# CutMonitor_Opto.net
KiCad netlist of a schematic drawn in Altium Designer
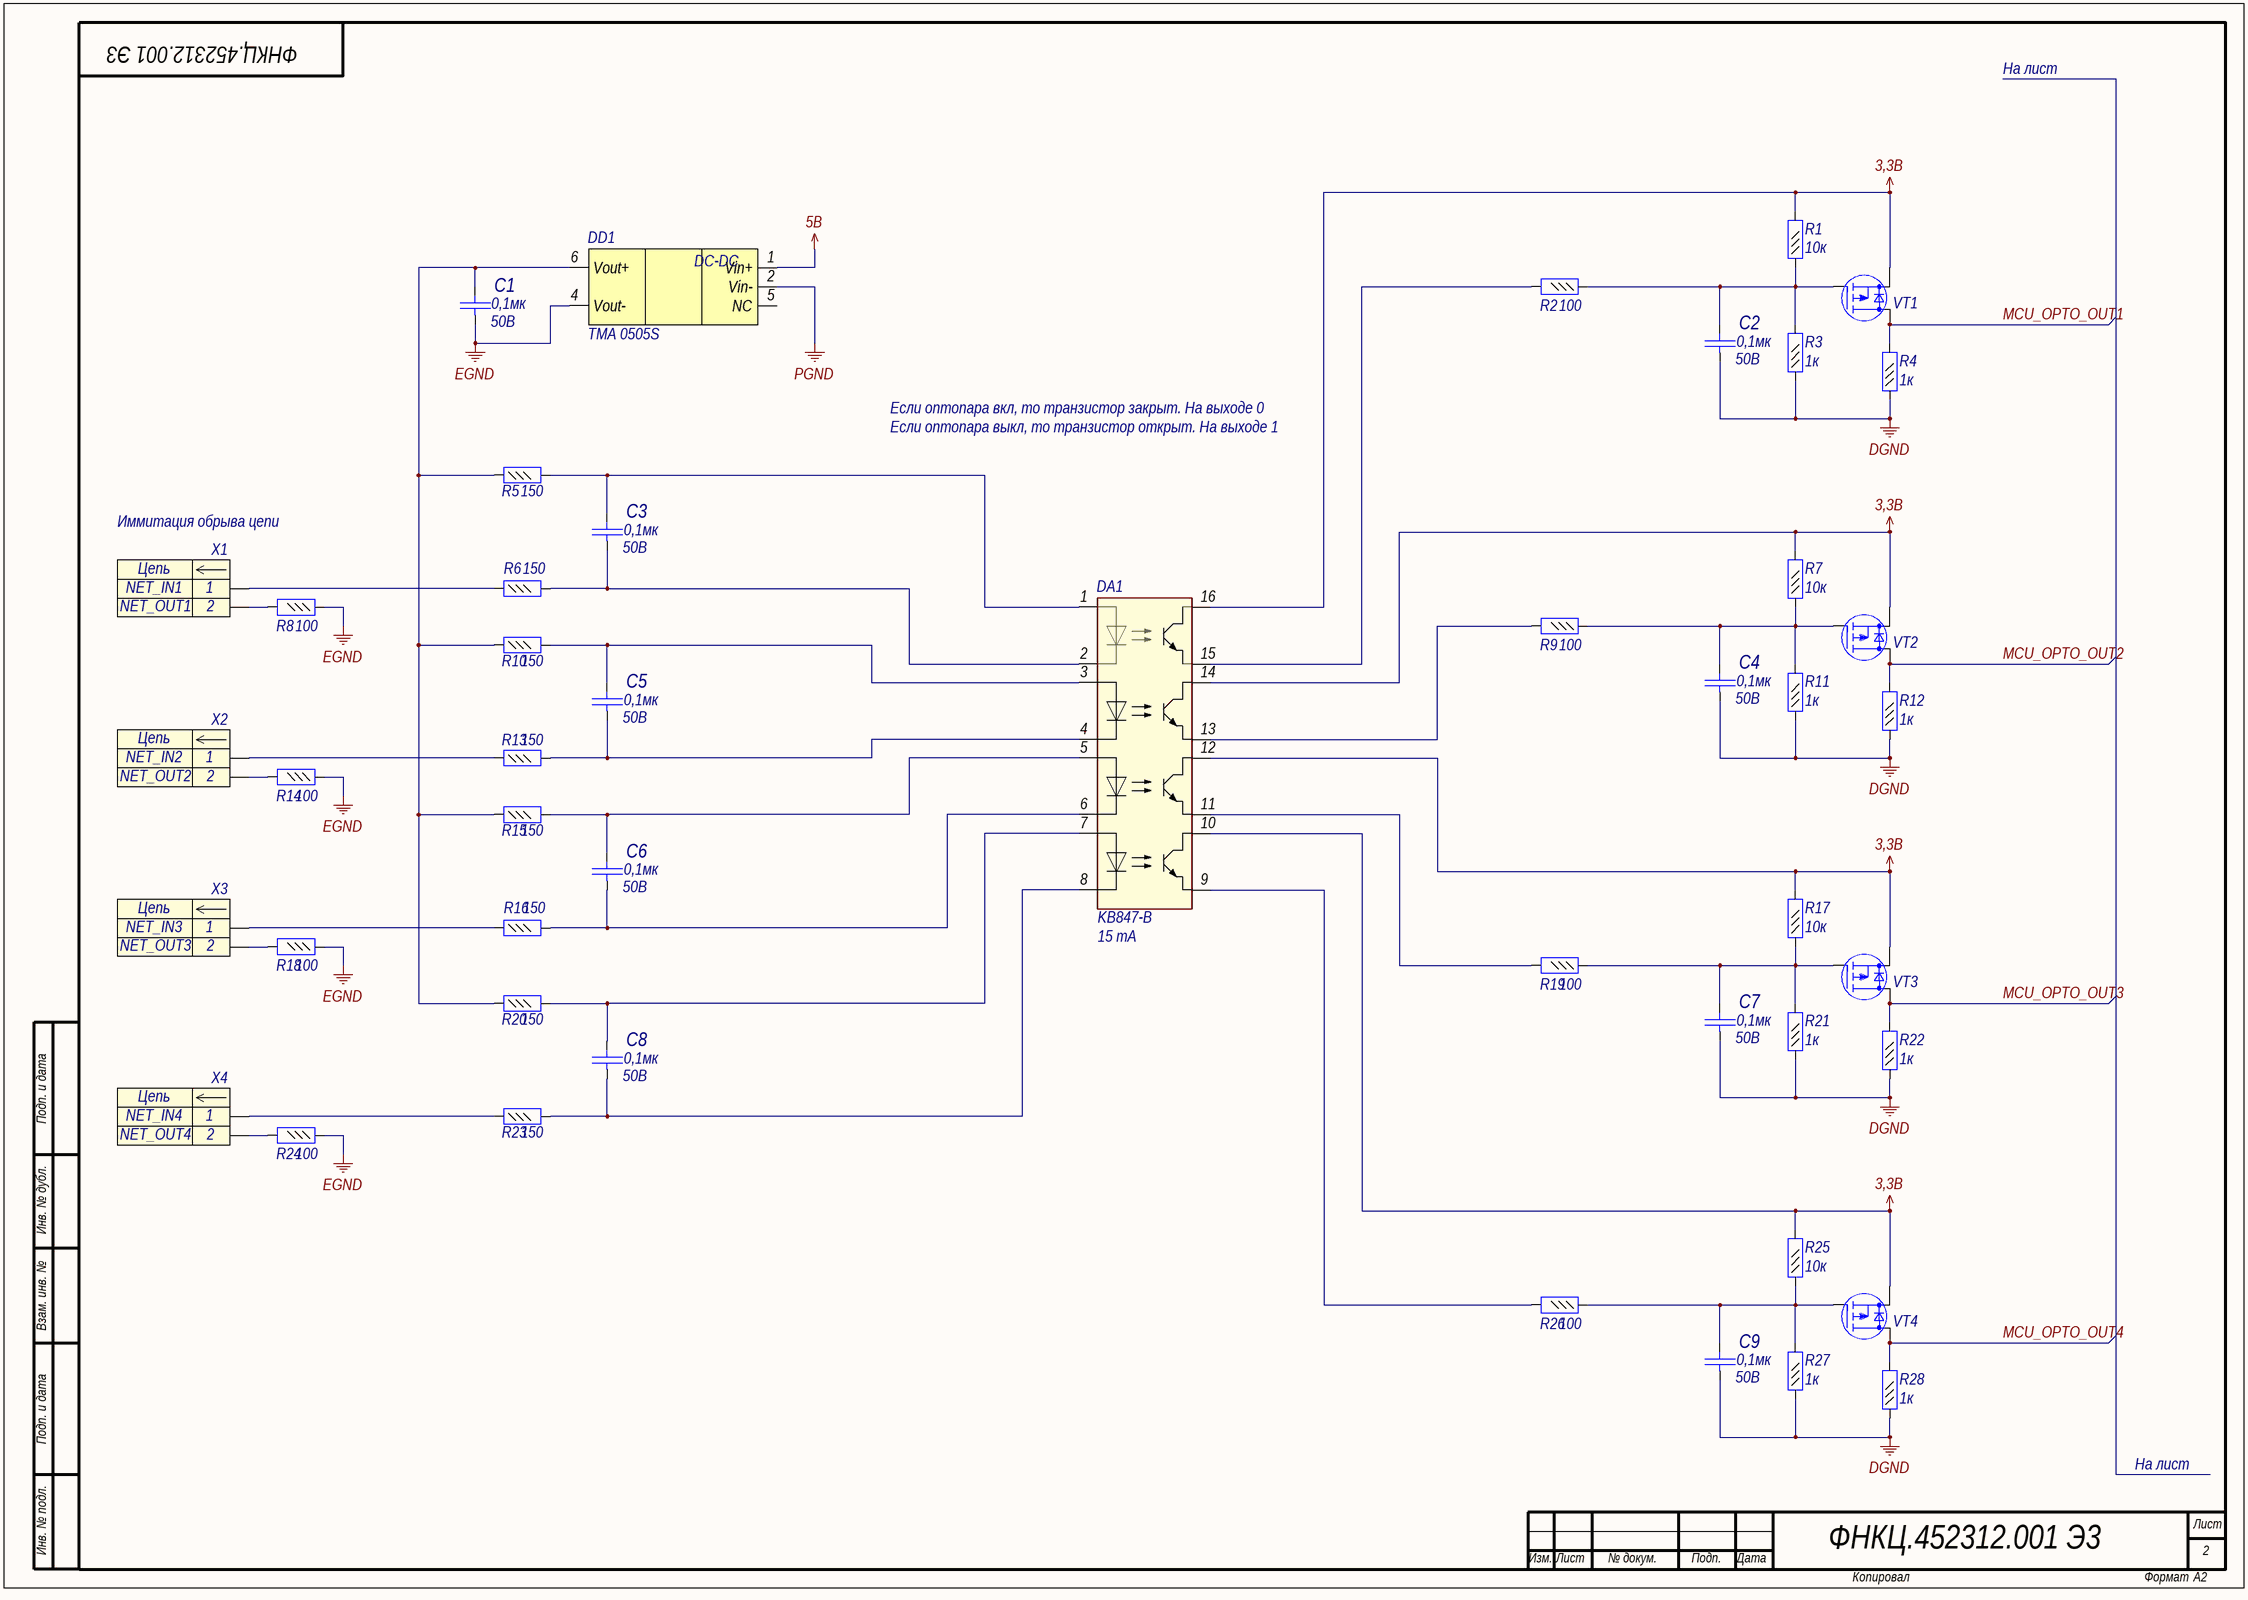
[diagram p0: CutMonitor_Opto.SchDoc]

(export (version "E")
  (design (tool "Eeschema 10.0.6"))
  (components
    (comp (ref "C1")
      (value "0,1мк")
      (footprint "C0603")
      (description "Конденсатор")
      (fields
        (field (name "VOLTAGE") "50B")
        (field (name "PART NUMBER") "GRM188R71H104KA93D")
        (field (name "Comment") "Capacitor")
      )
      (libsource (lib "MOP44") (part "Capacitor"))
    )
    (comp (ref "C2")
      (value "0,1мк")
      (footprint "C0603")
      (description "Конденсатор")
      (fields
        (field (name "VOLTAGE") "50B")
        (field (name "PART NUMBER") "GRM188R71H104KA93D")
        (field (name "Comment") "Capacitor")
      )
      (libsource (lib "MOP44") (part "Capacitor"))
    )
    (comp (ref "C3")
      (value "0,1мк")
      (footprint "C0603")
      (description "Конденсатор")
      (fields
        (field (name "VOLTAGE") "50B")
        (field (name "PART NUMBER") "GRM188R71H104KA93D")
        (field (name "Comment") "Capacitor")
      )
      (libsource (lib "MOP44") (part "Capacitor"))
    )
    (comp (ref "C4")
      (value "0,1мк")
      (footprint "C0603")
      (description "Конденсатор")
      (fields
        (field (name "VOLTAGE") "50B")
        (field (name "PART NUMBER") "GRM188R71H104KA93D")
        (field (name "Comment") "Capacitor")
      )
      (libsource (lib "MOP44") (part "Capacitor"))
    )
    (comp (ref "C5")
      (value "0,1мк")
      (footprint "C0603")
      (description "Конденсатор")
      (fields
        (field (name "VOLTAGE") "50B")
        (field (name "PART NUMBER") "GRM188R71H104KA93D")
        (field (name "Comment") "Capacitor")
      )
      (libsource (lib "MOP44") (part "Capacitor"))
    )
    (comp (ref "C6")
      (value "0,1мк")
      (footprint "C0603")
      (description "Конденсатор")
      (fields
        (field (name "VOLTAGE") "50B")
        (field (name "PART NUMBER") "GRM188R71H104KA93D")
        (field (name "Comment") "Capacitor")
      )
      (libsource (lib "MOP44") (part "Capacitor"))
    )
    (comp (ref "C7")
      (value "0,1мк")
      (footprint "C0603")
      (description "Конденсатор")
      (fields
        (field (name "VOLTAGE") "50B")
        (field (name "PART NUMBER") "GRM188R71H104KA93D")
        (field (name "Comment") "Capacitor")
      )
      (libsource (lib "MOP44") (part "Capacitor"))
    )
    (comp (ref "C8")
      (value "0,1мк")
      (footprint "C0603")
      (description "Конденсатор")
      (fields
        (field (name "VOLTAGE") "50B")
        (field (name "PART NUMBER") "GRM188R71H104KA93D")
        (field (name "Comment") "Capacitor")
      )
      (libsource (lib "MOP44") (part "Capacitor"))
    )
    (comp (ref "C9")
      (value "0,1мк")
      (footprint "C0603")
      (description "Конденсатор")
      (fields
        (field (name "VOLTAGE") "50B")
        (field (name "PART NUMBER") "GRM188R71H104KA93D")
        (field (name "Comment") "Capacitor")
      )
      (libsource (lib "MOP44") (part "Capacitor"))
    )
    (comp (ref "DA1")
      (value "OPTO-4")
      (footprint "OPTO-16")
      (description "Опторазвязка х4")
      (fields (field (name "PART NUMBER") "KB847-B") (field (name "MANUFACTURER") "Kingbright"))
      (libsource (lib "MOP44") (part "OPTO-4"))
    )
    (comp (ref "DD1")
      (value "TMA")
      (footprint "TMH0505")
      (description "DC/DC преобразователь")
      (fields (field (name "PART NUMBER") "TMA 0505S") (field (name "MANUFACTURER") "Traco Power"))
      (libsource (lib "MOP44") (part "TMA"))
    )
    (comp (ref "R1")
      (value "10к")
      (footprint "R0603")
      (description "Резистор")
      (fields (field (name "PART NUMBER") "RC0603FR-0710KL") (field (name "POWER") "0,062Вт"))
      (libsource (lib "MOP44") (part "Resistor_0,062Вт"))
    )
    (comp (ref "R2")
      (value "100")
      (footprint "R0603")
      (description "Резистор")
      (fields (field (name "PART NUMBER") "RC0603FR-07100RL") (field (name "POWER") "0,062Вт"))
      (libsource (lib "") (part "Resistor_0,062Вт_2"))
    )
    (comp (ref "R3")
      (value "1к")
      (footprint "R0603")
      (description "Резистор")
      (fields (field (name "PART NUMBER") "RC0603FR-071KL") (field (name "POWER") "0,062Вт"))
      (libsource (lib "MOP44") (part "Resistor_0,062Вт"))
    )
    (comp (ref "R4")
      (value "1к")
      (footprint "R0603")
      (description "Резистор")
      (fields (field (name "PART NUMBER") "RC0603FR-071KL") (field (name "POWER") "0,062Вт"))
      (libsource (lib "MOP44") (part "Resistor_0,062Вт"))
    )
    (comp (ref "R5")
      (value "150")
      (footprint "R0603")
      (description "Резистор")
      (fields (field (name "PART NUMBER") "RC0603FR-07150RL") (field (name "POWER") "0,062Вт"))
      (libsource (lib "") (part "Resistor_0,062Вт_1"))
    )
    (comp (ref "R6")
      (value "150")
      (footprint "R0603")
      (description "Резистор")
      (fields (field (name "PART NUMBER") "RC0603FR-07150RL") (field (name "POWER") "0,062Вт"))
      (libsource (lib "") (part "Resistor_0,062Вт_1"))
    )
    (comp (ref "R7")
      (value "10к")
      (footprint "R0603")
      (description "Резистор")
      (fields (field (name "PART NUMBER") "RC0603FR-0710KL") (field (name "POWER") "0,062Вт"))
      (libsource (lib "MOP44") (part "Resistor_0,062Вт"))
    )
    (comp (ref "R8")
      (value "100")
      (footprint "R0603")
      (description "Резистор")
      (fields (field (name "PART NUMBER") "RC0603FR-07100RL") (field (name "POWER") "0,062Вт"))
      (libsource (lib "") (part "Resistor_0,062Вт_2"))
    )
    (comp (ref "R9")
      (value "100")
      (footprint "R0603")
      (description "Резистор")
      (fields (field (name "PART NUMBER") "RC0603FR-07100RL") (field (name "POWER") "0,062Вт"))
      (libsource (lib "") (part "Resistor_0,062Вт_2"))
    )
    (comp (ref "R10")
      (value "150")
      (footprint "R0603")
      (description "Резистор")
      (fields (field (name "PART NUMBER") "RC0603FR-07150RL") (field (name "POWER") "0,062Вт"))
      (libsource (lib "") (part "Resistor_0,062Вт_1"))
    )
    (comp (ref "R11")
      (value "1к")
      (footprint "R0603")
      (description "Резистор")
      (fields (field (name "PART NUMBER") "RC0603FR-071KL") (field (name "POWER") "0,062Вт"))
      (libsource (lib "MOP44") (part "Resistor_0,062Вт"))
    )
    (comp (ref "R12")
      (value "1к")
      (footprint "R0603")
      (description "Резистор")
      (fields (field (name "PART NUMBER") "RC0603FR-071KL") (field (name "POWER") "0,062Вт"))
      (libsource (lib "MOP44") (part "Resistor_0,062Вт"))
    )
    (comp (ref "R13")
      (value "150")
      (footprint "R0603")
      (description "Резистор")
      (fields (field (name "PART NUMBER") "RC0603FR-07150RL") (field (name "POWER") "0,062Вт"))
      (libsource (lib "") (part "Resistor_0,062Вт_1"))
    )
    (comp (ref "R14")
      (value "100")
      (footprint "R0603")
      (description "Резистор")
      (fields (field (name "PART NUMBER") "RC0603FR-07100RL") (field (name "POWER") "0,062Вт"))
      (libsource (lib "") (part "Resistor_0,062Вт_2"))
    )
    (comp (ref "R15")
      (value "150")
      (footprint "R0603")
      (description "Резистор")
      (fields (field (name "PART NUMBER") "RC0603FR-07150RL") (field (name "POWER") "0,062Вт"))
      (libsource (lib "") (part "Resistor_0,062Вт_1"))
    )
    (comp (ref "R16")
      (value "150")
      (footprint "R0603")
      (description "Резистор")
      (fields (field (name "PART NUMBER") "RC0603FR-07150RL") (field (name "POWER") "0,062Вт"))
      (libsource (lib "") (part "Resistor_0,062Вт_1"))
    )
    (comp (ref "R17")
      (value "10к")
      (footprint "R0603")
      (description "Резистор")
      (fields (field (name "PART NUMBER") "RC0603FR-0710KL") (field (name "POWER") "0,062Вт"))
      (libsource (lib "MOP44") (part "Resistor_0,062Вт"))
    )
    (comp (ref "R18")
      (value "100")
      (footprint "R0603")
      (description "Резистор")
      (fields (field (name "PART NUMBER") "RC0603FR-07100RL") (field (name "POWER") "0,062Вт"))
      (libsource (lib "") (part "Resistor_0,062Вт_2"))
    )
    (comp (ref "R19")
      (value "100")
      (footprint "R0603")
      (description "Резистор")
      (fields (field (name "PART NUMBER") "RC0603FR-07100RL") (field (name "POWER") "0,062Вт"))
      (libsource (lib "") (part "Resistor_0,062Вт_2"))
    )
    (comp (ref "R20")
      (value "150")
      (footprint "R0603")
      (description "Резистор")
      (fields (field (name "PART NUMBER") "RC0603FR-07150RL") (field (name "POWER") "0,062Вт"))
      (libsource (lib "") (part "Resistor_0,062Вт_1"))
    )
    (comp (ref "R21")
      (value "1к")
      (footprint "R0603")
      (description "Резистор")
      (fields (field (name "PART NUMBER") "RC0603FR-071KL") (field (name "POWER") "0,062Вт"))
      (libsource (lib "MOP44") (part "Resistor_0,062Вт"))
    )
    (comp (ref "R22")
      (value "1к")
      (footprint "R0603")
      (description "Резистор")
      (fields (field (name "PART NUMBER") "RC0603FR-071KL") (field (name "POWER") "0,062Вт"))
      (libsource (lib "MOP44") (part "Resistor_0,062Вт"))
    )
    (comp (ref "R23")
      (value "150")
      (footprint "R0603")
      (description "Резистор")
      (fields (field (name "PART NUMBER") "RC0603FR-07150RL") (field (name "POWER") "0,062Вт"))
      (libsource (lib "") (part "Resistor_0,062Вт_1"))
    )
    (comp (ref "R24")
      (value "100")
      (footprint "R0603")
      (description "Резистор")
      (fields (field (name "PART NUMBER") "RC0603FR-07100RL") (field (name "POWER") "0,062Вт"))
      (libsource (lib "") (part "Resistor_0,062Вт_2"))
    )
    (comp (ref "R25")
      (value "10к")
      (footprint "R0603")
      (description "Резистор")
      (fields (field (name "PART NUMBER") "RC0603FR-0710KL") (field (name "POWER") "0,062Вт"))
      (libsource (lib "MOP44") (part "Resistor_0,062Вт"))
    )
    (comp (ref "R26")
      (value "100")
      (footprint "R0603")
      (description "Резистор")
      (fields (field (name "PART NUMBER") "RC0603FR-07100RL") (field (name "POWER") "0,062Вт"))
      (libsource (lib "") (part "Resistor_0,062Вт_2"))
    )
    (comp (ref "R27")
      (value "1к")
      (footprint "R0603")
      (description "Резистор")
      (fields (field (name "PART NUMBER") "RC0603FR-071KL") (field (name "POWER") "0,062Вт"))
      (libsource (lib "MOP44") (part "Resistor_0,062Вт"))
    )
    (comp (ref "R28")
      (value "1к")
      (footprint "R0603")
      (description "Резистор")
      (fields (field (name "PART NUMBER") "RC0603FR-071KL") (field (name "POWER") "0,062Вт"))
      (libsource (lib "MOP44") (part "Resistor_0,062Вт"))
    )
    (comp (ref "VT1")
      (value "P-MOSFET")
      (footprint "SOT23-3")
      (description "N-MOSFET")
      (fields
        (field (name "PART NUMBER") "IRLML2244TRPbF")
        (field (name "MANUFACTURER") "International Rectifier")
      )
      (libsource (lib "MOP44") (part "P-MOSFET"))
    )
    (comp (ref "VT2")
      (value "P-MOSFET")
      (footprint "SOT23-3")
      (description "N-MOSFET")
      (fields
        (field (name "PART NUMBER") "IRLML2244TRPbF")
        (field (name "MANUFACTURER") "International Rectifier")
      )
      (libsource (lib "MOP44") (part "P-MOSFET"))
    )
    (comp (ref "VT3")
      (value "P-MOSFET")
      (footprint "SOT23-3")
      (description "N-MOSFET")
      (fields
        (field (name "PART NUMBER") "IRLML2244TRPbF")
        (field (name "MANUFACTURER") "International Rectifier")
      )
      (libsource (lib "MOP44") (part "P-MOSFET"))
    )
    (comp (ref "VT4")
      (value "P-MOSFET")
      (footprint "SOT23-3")
      (description "N-MOSFET")
      (fields
        (field (name "PART NUMBER") "IRLML2244TRPbF")
        (field (name "MANUFACTURER") "International Rectifier")
      )
      (libsource (lib "MOP44") (part "P-MOSFET"))
    )
    (comp (ref "X1")
      (value "~")
      (footprint "JUMPER_2.54")
      (description "Разъем - 2 конт. вилка")
      (libsource (lib "MOP44") (part "Header_2_plg"))
    )
    (comp (ref "X2")
      (value "~")
      (footprint "JUMPER_2.54")
      (description "Разъем - 2 конт. вилка")
      (libsource (lib "MOP44") (part "Header_2_plg"))
    )
    (comp (ref "X3")
      (value "~")
      (footprint "JUMPER_2.54")
      (description "Разъем - 2 конт. вилка")
      (libsource (lib "MOP44") (part "Header_2_plg"))
    )
    (comp (ref "X4")
      (value "~")
      (footprint "JUMPER_2.54")
      (description "Разъем - 2 конт. вилка")
      (libsource (lib "MOP44") (part "Header_2_plg"))
    )
  )
  (nets
    (net (code "1") (name "/MCU_OPTO_OUT1") (class "Default")
      (node (ref "R4") (pin "2") (pinfunction "2_2") (pintype "passive"))
      (node (ref "VT1") (pin "2") (pinfunction "D_2") (pintype "passive"))
    )
    (net (code "2") (name "/MCU_OPTO_OUT2") (class "Default")
      (node (ref "R12") (pin "2") (pinfunction "2_2") (pintype "passive"))
      (node (ref "VT2") (pin "2") (pinfunction "D_2") (pintype "passive"))
    )
    (net (code "3") (name "/MCU_OPTO_OUT3") (class "Default")
      (node (ref "R22") (pin "2") (pinfunction "2_2") (pintype "passive"))
      (node (ref "VT3") (pin "2") (pinfunction "D_2") (pintype "passive"))
    )
    (net (code "4") (name "/MCU_OPTO_OUT4") (class "Default")
      (node (ref "R28") (pin "2") (pinfunction "2_2") (pintype "passive"))
      (node (ref "VT4") (pin "2") (pinfunction "D_2") (pintype "passive"))
    )
    (net (code "5") (name "3,3В") (class "Default")
      (node (ref "DA1") (pin "10") (pintype "passive"))
      (node (ref "DA1") (pin "12") (pintype "passive"))
      (node (ref "DA1") (pin "14") (pintype "passive"))
      (node (ref "DA1") (pin "16") (pintype "passive"))
      (node (ref "R1") (pin "2") (pinfunction "2_2") (pintype "passive"))
      (node (ref "R17") (pin "2") (pinfunction "2_2") (pintype "passive"))
      (node (ref "R25") (pin "2") (pinfunction "2_2") (pintype "passive"))
      (node (ref "R7") (pin "2") (pinfunction "2_2") (pintype "passive"))
      (node (ref "VT1") (pin "3") (pinfunction "S_3") (pintype "passive"))
      (node (ref "VT2") (pin "3") (pinfunction "S_3") (pintype "passive"))
      (node (ref "VT3") (pin "3") (pinfunction "S_3") (pintype "passive"))
      (node (ref "VT4") (pin "3") (pinfunction "S_3") (pintype "passive"))
    )
    (net (code "6") (name "5В") (class "Default")
      (node (ref "DD1") (pin "1") (pinfunction "Vin+_1") (pintype "passive"))
    )
    (net (code "7") (name "DGND") (class "Default")
      (node (ref "C2") (pin "1") (pinfunction "1_1") (pintype "passive"))
      (node (ref "C4") (pin "1") (pinfunction "1_1") (pintype "passive"))
      (node (ref "C7") (pin "1") (pinfunction "1_1") (pintype "passive"))
      (node (ref "C9") (pin "1") (pinfunction "1_1") (pintype "passive"))
      (node (ref "R11") (pin "1") (pinfunction "1_1") (pintype "passive"))
      (node (ref "R12") (pin "1") (pinfunction "1_1") (pintype "passive"))
      (node (ref "R21") (pin "1") (pinfunction "1_1") (pintype "passive"))
      (node (ref "R22") (pin "1") (pinfunction "1_1") (pintype "passive"))
      (node (ref "R27") (pin "1") (pinfunction "1_1") (pintype "passive"))
      (node (ref "R28") (pin "1") (pinfunction "1_1") (pintype "passive"))
      (node (ref "R3") (pin "1") (pinfunction "1_1") (pintype "passive"))
      (node (ref "R4") (pin "1") (pinfunction "1_1") (pintype "passive"))
    )
    (net (code "8") (name "EGND") (class "Default")
      (node (ref "C1") (pin "1") (pinfunction "1_1") (pintype "passive"))
      (node (ref "DD1") (pin "4") (pinfunction "Vout-_4") (pintype "passive"))
      (node (ref "R14") (pin "1") (pinfunction "1_1") (pintype "passive"))
      (node (ref "R18") (pin "1") (pinfunction "1_1") (pintype "passive"))
      (node (ref "R24") (pin "1") (pinfunction "1_1") (pintype "passive"))
      (node (ref "R8") (pin "1") (pinfunction "1_1") (pintype "passive"))
    )
    (net (code "9") (name "Net-(C3-Pad1)") (class "Default")
      (node (ref "C3") (pin "1") (pinfunction "1_1") (pintype "passive"))
      (node (ref "DA1") (pin "2") (pintype "passive"))
      (node (ref "R6") (pin "2") (pinfunction "2_2") (pintype "passive"))
    )
    (net (code "10") (name "Net-(C3-Pad2)") (class "Default")
      (node (ref "C3") (pin "2") (pinfunction "2_2") (pintype "passive"))
      (node (ref "DA1") (pin "1") (pintype "passive"))
      (node (ref "R5") (pin "2") (pinfunction "2_2") (pintype "passive"))
    )
    (net (code "11") (name "Net-(C5-Pad1)") (class "Default")
      (node (ref "C5") (pin "1") (pinfunction "1_1") (pintype "passive"))
      (node (ref "DA1") (pin "4") (pintype "passive"))
      (node (ref "R13") (pin "2") (pinfunction "2_2") (pintype "passive"))
    )
    (net (code "12") (name "Net-(C5-Pad2)") (class "Default")
      (node (ref "C5") (pin "2") (pinfunction "2_2") (pintype "passive"))
      (node (ref "DA1") (pin "3") (pintype "passive"))
      (node (ref "R10") (pin "2") (pinfunction "2_2") (pintype "passive"))
    )
    (net (code "13") (name "Net-(C6-Pad1)") (class "Default")
      (node (ref "C6") (pin "1") (pinfunction "1_1") (pintype "passive"))
      (node (ref "DA1") (pin "6") (pintype "passive"))
      (node (ref "R16") (pin "2") (pinfunction "2_2") (pintype "passive"))
    )
    (net (code "14") (name "Net-(C6-Pad2)") (class "Default")
      (node (ref "C6") (pin "2") (pinfunction "2_2") (pintype "passive"))
      (node (ref "DA1") (pin "5") (pintype "passive"))
      (node (ref "R15") (pin "2") (pinfunction "2_2") (pintype "passive"))
    )
    (net (code "15") (name "Net-(C8-Pad1)") (class "Default")
      (node (ref "C8") (pin "1") (pinfunction "1_1") (pintype "passive"))
      (node (ref "DA1") (pin "8") (pintype "passive"))
      (node (ref "R23") (pin "2") (pinfunction "2_2") (pintype "passive"))
    )
    (net (code "16") (name "Net-(C8-Pad2)") (class "Default")
      (node (ref "C8") (pin "2") (pinfunction "2_2") (pintype "passive"))
      (node (ref "DA1") (pin "7") (pintype "passive"))
      (node (ref "R20") (pin "2") (pinfunction "2_2") (pintype "passive"))
    )
    (net (code "17") (name "Net-(DA1-Pad9)") (class "Default")
      (node (ref "DA1") (pin "9") (pintype "passive"))
      (node (ref "R26") (pin "2") (pinfunction "2_2") (pintype "passive"))
    )
    (net (code "18") (name "Net-(DA1-Pad11)") (class "Default")
      (node (ref "DA1") (pin "11") (pintype "passive"))
      (node (ref "R19") (pin "2") (pinfunction "2_2") (pintype "passive"))
    )
    (net (code "19") (name "Net-(DA1-Pad13)") (class "Default")
      (node (ref "DA1") (pin "13") (pintype "passive"))
      (node (ref "R9") (pin "2") (pinfunction "2_2") (pintype "passive"))
    )
    (net (code "20") (name "Net-(DA1-Pad15)") (class "Default")
      (node (ref "DA1") (pin "15") (pintype "passive"))
      (node (ref "R2") (pin "2") (pinfunction "2_2") (pintype "passive"))
    )
    (net (code "21") (name "Net-(DD1-Vout+)") (class "Default")
      (node (ref "C1") (pin "2") (pinfunction "2_2") (pintype "passive"))
      (node (ref "DD1") (pin "6") (pinfunction "Vout+_6") (pintype "passive"))
      (node (ref "R10") (pin "1") (pinfunction "1_1") (pintype "passive"))
      (node (ref "R15") (pin "1") (pinfunction "1_1") (pintype "passive"))
      (node (ref "R20") (pin "1") (pinfunction "1_1") (pintype "passive"))
      (node (ref "R5") (pin "1") (pinfunction "1_1") (pintype "passive"))
    )
    (net (code "22") (name "Net-(R6-Pad1)") (class "Default")
      (node (ref "R6") (pin "1") (pinfunction "1_1") (pintype "passive"))
      (node (ref "X1") (pin "1") (pinfunction "1_1") (pintype "passive"))
    )
    (net (code "23") (name "Net-(R8-Pad2)") (class "Default")
      (node (ref "R8") (pin "2") (pinfunction "2_2") (pintype "passive"))
      (node (ref "X1") (pin "2") (pinfunction "2_2") (pintype "passive"))
    )
    (net (code "24") (name "Net-(R13-Pad1)") (class "Default")
      (node (ref "R13") (pin "1") (pinfunction "1_1") (pintype "passive"))
      (node (ref "X2") (pin "1") (pinfunction "1_1") (pintype "passive"))
    )
    (net (code "25") (name "Net-(R14-Pad2)") (class "Default")
      (node (ref "R14") (pin "2") (pinfunction "2_2") (pintype "passive"))
      (node (ref "X2") (pin "2") (pinfunction "2_2") (pintype "passive"))
    )
    (net (code "26") (name "Net-(R16-Pad1)") (class "Default")
      (node (ref "R16") (pin "1") (pinfunction "1_1") (pintype "passive"))
      (node (ref "X3") (pin "1") (pinfunction "1_1") (pintype "passive"))
    )
    (net (code "27") (name "Net-(R18-Pad2)") (class "Default")
      (node (ref "R18") (pin "2") (pinfunction "2_2") (pintype "passive"))
      (node (ref "X3") (pin "2") (pinfunction "2_2") (pintype "passive"))
    )
    (net (code "28") (name "Net-(R23-Pad1)") (class "Default")
      (node (ref "R23") (pin "1") (pinfunction "1_1") (pintype "passive"))
      (node (ref "X4") (pin "1") (pinfunction "1_1") (pintype "passive"))
    )
    (net (code "29") (name "Net-(R24-Pad2)") (class "Default")
      (node (ref "R24") (pin "2") (pinfunction "2_2") (pintype "passive"))
      (node (ref "X4") (pin "2") (pinfunction "2_2") (pintype "passive"))
    )
    (net (code "30") (name "Net-(VT1-G)") (class "Default")
      (node (ref "C2") (pin "2") (pinfunction "2_2") (pintype "passive"))
      (node (ref "R1") (pin "1") (pinfunction "1_1") (pintype "passive"))
      (node (ref "R2") (pin "1") (pinfunction "1_1") (pintype "passive"))
      (node (ref "R3") (pin "2") (pinfunction "2_2") (pintype "passive"))
      (node (ref "VT1") (pin "1") (pinfunction "G_1") (pintype "passive"))
    )
    (net (code "31") (name "Net-(VT2-G)") (class "Default")
      (node (ref "C4") (pin "2") (pinfunction "2_2") (pintype "passive"))
      (node (ref "R11") (pin "2") (pinfunction "2_2") (pintype "passive"))
      (node (ref "R7") (pin "1") (pinfunction "1_1") (pintype "passive"))
      (node (ref "R9") (pin "1") (pinfunction "1_1") (pintype "passive"))
      (node (ref "VT2") (pin "1") (pinfunction "G_1") (pintype "passive"))
    )
    (net (code "32") (name "Net-(VT3-G)") (class "Default")
      (node (ref "C7") (pin "2") (pinfunction "2_2") (pintype "passive"))
      (node (ref "R17") (pin "1") (pinfunction "1_1") (pintype "passive"))
      (node (ref "R19") (pin "1") (pinfunction "1_1") (pintype "passive"))
      (node (ref "R21") (pin "2") (pinfunction "2_2") (pintype "passive"))
      (node (ref "VT3") (pin "1") (pinfunction "G_1") (pintype "passive"))
    )
    (net (code "33") (name "Net-(VT4-G)") (class "Default")
      (node (ref "C9") (pin "2") (pinfunction "2_2") (pintype "passive"))
      (node (ref "R25") (pin "1") (pinfunction "1_1") (pintype "passive"))
      (node (ref "R26") (pin "1") (pinfunction "1_1") (pintype "passive"))
      (node (ref "R27") (pin "2") (pinfunction "2_2") (pintype "passive"))
      (node (ref "VT4") (pin "1") (pinfunction "G_1") (pintype "passive"))
    )
    (net (code "34") (name "PGND") (class "Default")
      (node (ref "DD1") (pin "2") (pinfunction "Vin-_2") (pintype "passive"))
    )
    (net (code "35") (name "unconnected-(DD1-NC-Pad5)") (class "Default")
      (node (ref "DD1") (pin "5") (pinfunction "NC_5") (pintype "passive"))
    )
  )
)
